# USB-hub.net
KiCad netlist of a schematic drawn in Altium Designer
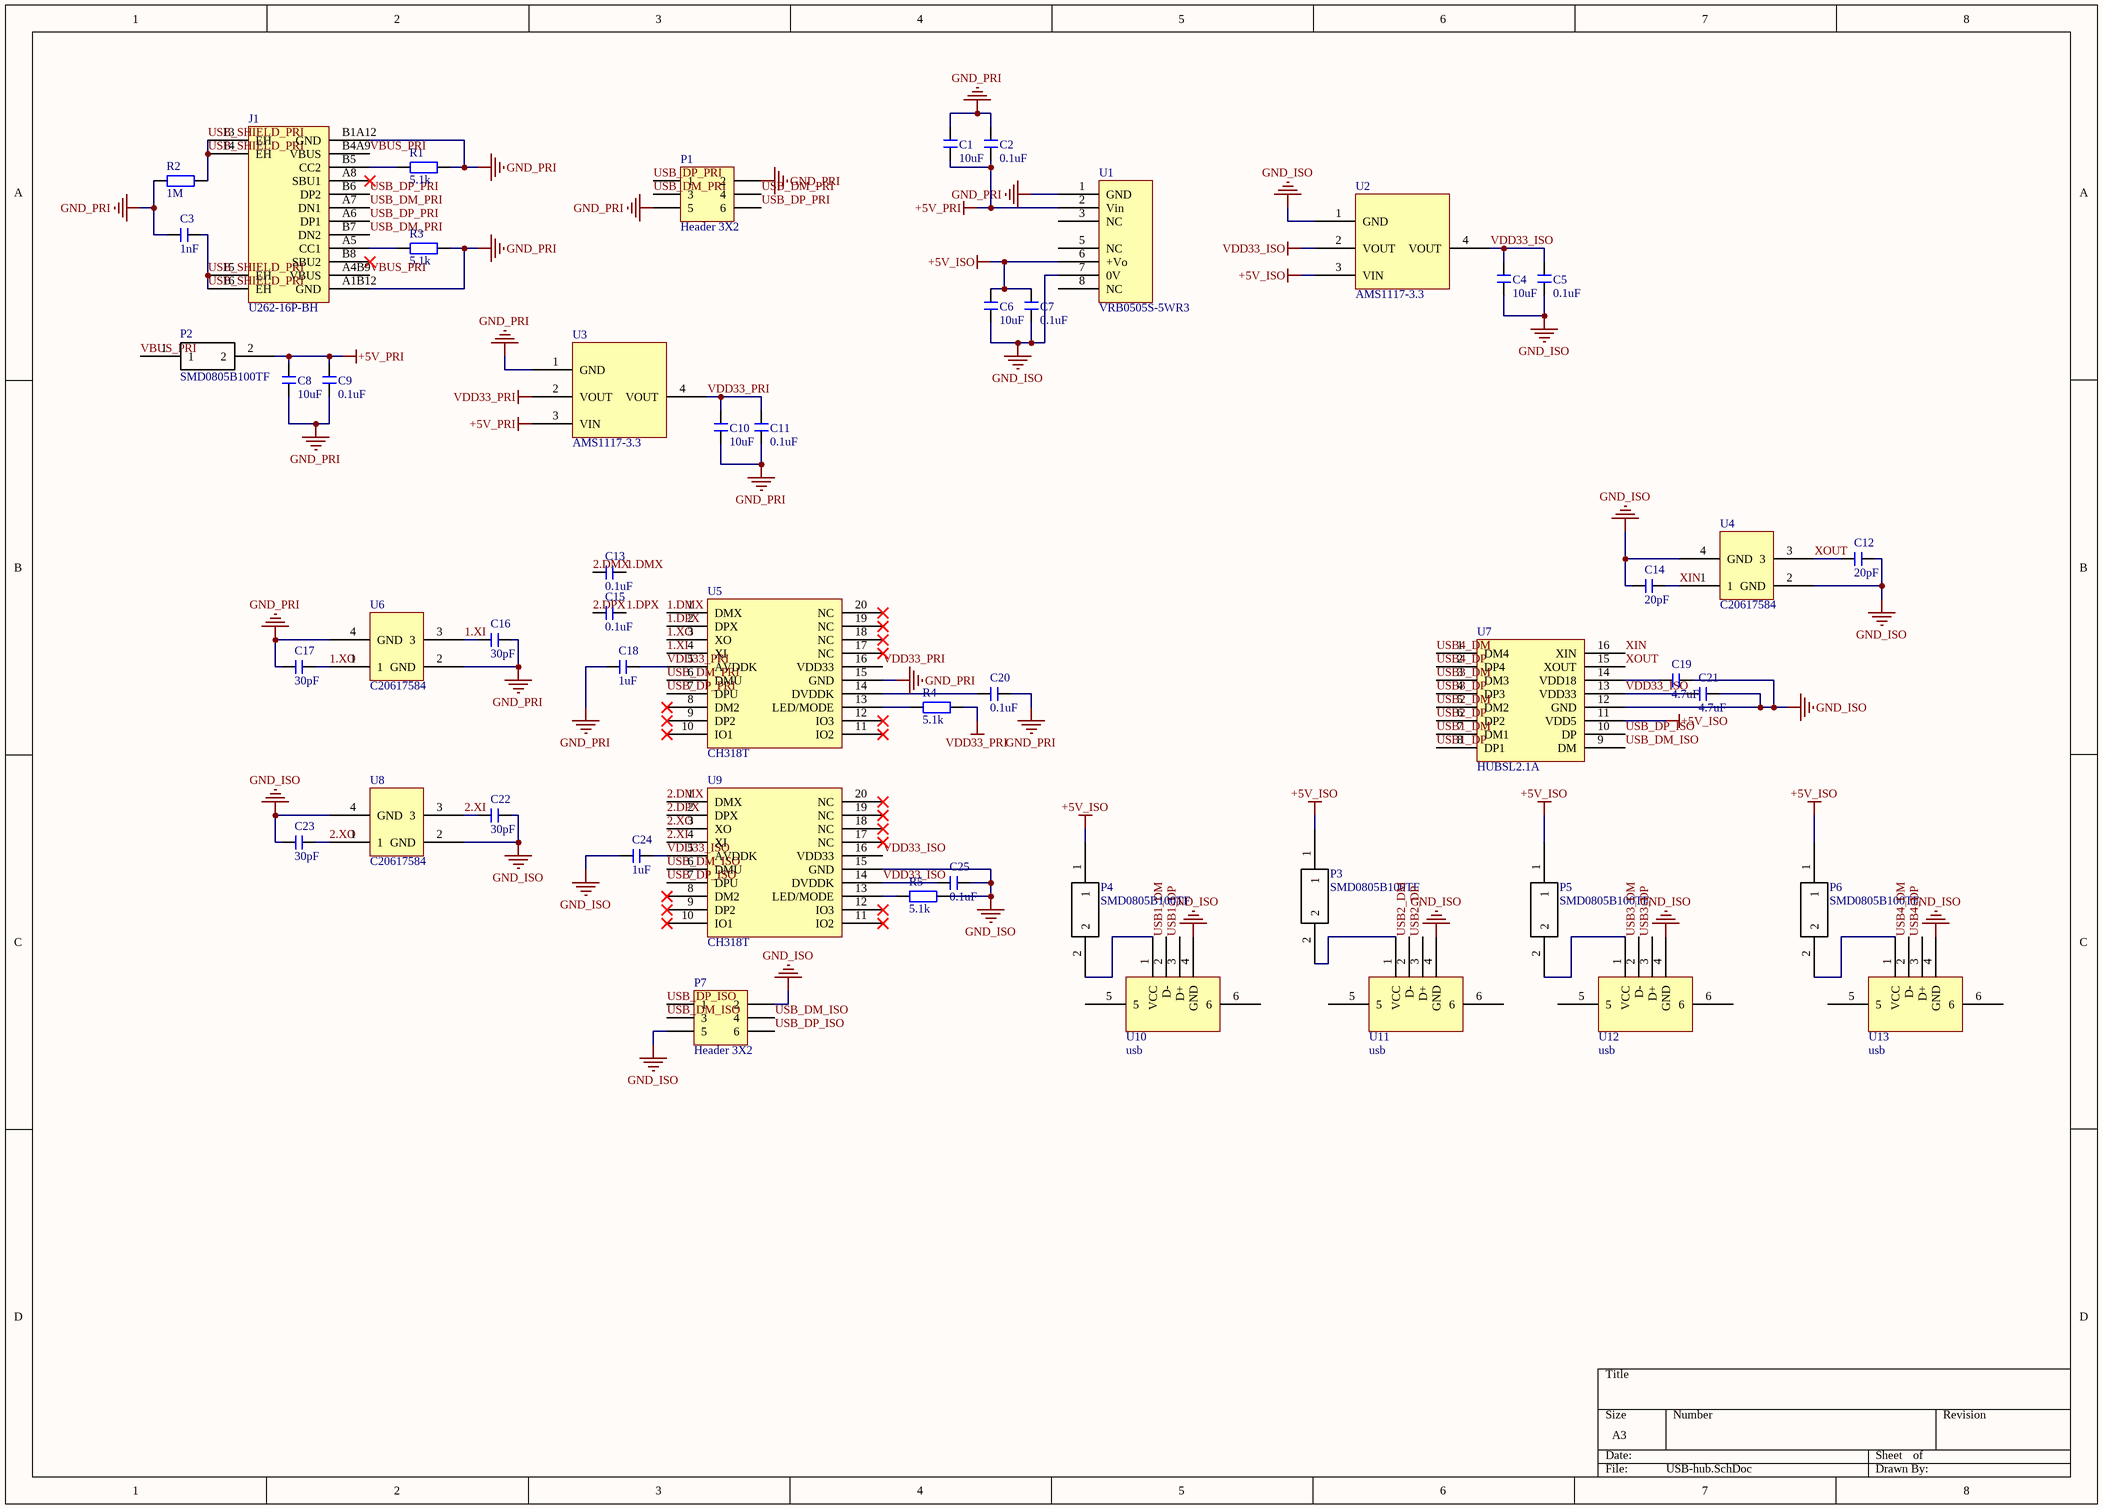
[diagram p0: USB-hub.SchDoc]

(export (version "E")
  (design (tool "Eeschema 10.0.6"))
  (components
    (comp (ref "C1")
      (value "10uF")
      (footprint "C 0603_L")
      (description "贴片电容")
      (libsource (lib "0.1 - 电阻-电容-电感") (part "C"))
    )
    (comp (ref "C2")
      (value "0.1uF")
      (footprint "C 0603_L")
      (description "贴片电容")
      (libsource (lib "0.1 - 电阻-电容-电感") (part "C"))
    )
    (comp (ref "C3")
      (value "1nF")
      (footprint "C 0603_L")
      (description "贴片电容")
      (libsource (lib "0.1 - 电阻-电容-电感") (part "C"))
    )
    (comp (ref "C4")
      (value "10uF")
      (footprint "C 0603_L")
      (description "贴片电容")
      (libsource (lib "0.1 - 电阻-电容-电感") (part "C"))
    )
    (comp (ref "C5")
      (value "0.1uF")
      (footprint "C 0603_L")
      (description "贴片电容")
      (libsource (lib "0.1 - 电阻-电容-电感") (part "C"))
    )
    (comp (ref "C6")
      (value "10uF")
      (footprint "C 0603_L")
      (description "贴片电容")
      (libsource (lib "0.1 - 电阻-电容-电感") (part "C"))
    )
    (comp (ref "C7")
      (value "0.1uF")
      (footprint "C 0603_L")
      (description "贴片电容")
      (libsource (lib "0.1 - 电阻-电容-电感") (part "C"))
    )
    (comp (ref "C8")
      (value "10uF")
      (footprint "C 0603_L")
      (description "贴片电容")
      (libsource (lib "0.1 - 电阻-电容-电感") (part "C"))
    )
    (comp (ref "C9")
      (value "0.1uF")
      (footprint "C 0603_L")
      (description "贴片电容")
      (libsource (lib "0.1 - 电阻-电容-电感") (part "C"))
    )
    (comp (ref "C10")
      (value "10uF")
      (footprint "C 0603_L")
      (description "贴片电容")
      (libsource (lib "0.1 - 电阻-电容-电感") (part "C"))
    )
    (comp (ref "C11")
      (value "0.1uF")
      (footprint "C 0603_L")
      (description "贴片电容")
      (libsource (lib "0.1 - 电阻-电容-电感") (part "C"))
    )
    (comp (ref "C12")
      (value "20pF")
      (footprint "C 0603_L")
      (description "贴片电容")
      (libsource (lib "0.1 - 电阻-电容-电感") (part "C"))
    )
    (comp (ref "C13")
      (value "0.1uF")
      (footprint "C 0603_L")
      (description "贴片电容")
      (libsource (lib "0.1 - 电阻-电容-电感") (part "C"))
    )
    (comp (ref "C14")
      (value "20pF")
      (footprint "C 0603_L")
      (description "贴片电容")
      (libsource (lib "0.1 - 电阻-电容-电感") (part "C"))
    )
    (comp (ref "C15")
      (value "0.1uF")
      (footprint "C 0603_L")
      (description "贴片电容")
      (libsource (lib "0.1 - 电阻-电容-电感") (part "C"))
    )
    (comp (ref "C16")
      (value "30pF")
      (footprint "C 0603_L")
      (description "贴片电容")
      (libsource (lib "0.1 - 电阻-电容-电感") (part "C"))
    )
    (comp (ref "C17")
      (value "30pF")
      (footprint "C 0603_L")
      (description "贴片电容")
      (libsource (lib "0.1 - 电阻-电容-电感") (part "C"))
    )
    (comp (ref "C18")
      (value "1uF")
      (footprint "C 0603_L")
      (description "贴片电容")
      (libsource (lib "0.1 - 电阻-电容-电感") (part "C"))
    )
    (comp (ref "C19")
      (value "4.7uF")
      (footprint "C 0603_L")
      (description "贴片电容")
      (libsource (lib "0.1 - 电阻-电容-电感") (part "C"))
    )
    (comp (ref "C20")
      (value "0.1uF")
      (footprint "C 0603_L")
      (description "贴片电容")
      (libsource (lib "0.1 - 电阻-电容-电感") (part "C"))
    )
    (comp (ref "C21")
      (value "4.7uF")
      (footprint "C 0603_L")
      (description "贴片电容")
      (libsource (lib "0.1 - 电阻-电容-电感") (part "C"))
    )
    (comp (ref "C22")
      (value "30pF")
      (footprint "C 0603_L")
      (description "贴片电容")
      (libsource (lib "0.1 - 电阻-电容-电感") (part "C"))
    )
    (comp (ref "C23")
      (value "30pF")
      (footprint "C 0603_L")
      (description "贴片电容")
      (libsource (lib "0.1 - 电阻-电容-电感") (part "C"))
    )
    (comp (ref "C24")
      (value "1uF")
      (footprint "C 0603_L")
      (description "贴片电容")
      (libsource (lib "0.1 - 电阻-电容-电感") (part "C"))
    )
    (comp (ref "C25")
      (value "0.1uF")
      (footprint "C 0603_L")
      (description "贴片电容")
      (libsource (lib "0.1 - 电阻-电容-电感") (part "C"))
    )
    (comp (ref "J1") (value "U262‑16P‑BH") (footprint "USB-hub") (libsource (lib "USB-hub") (part "type_c")))
    (comp (ref "P1")
      (value "Header 3X2")
      (footprint "SOT-6")
      (description "Header, 3-Pin, Dual row")
      (fields (field (name "PUBLISHER") "Altium Limited"))
      (libsource (lib "Miscellaneous Connectors") (part "Header 3X2"))
    )
    (comp (ref "P2")
      (value "SMD0805B100TF")
      (footprint "SMD0805B100TF")
      (libsource (lib "USB-hub") (part "SMD0805B100TF"))
    )
    (comp (ref "P3")
      (value "SMD0805B100TF")
      (footprint "SMD0805B100TF")
      (libsource (lib "USB-hub") (part "SMD0805B100TF"))
    )
    (comp (ref "P4")
      (value "SMD0805B100TF")
      (footprint "SMD0805B100TF")
      (libsource (lib "USB-hub") (part "SMD0805B100TF"))
    )
    (comp (ref "P5")
      (value "SMD0805B100TF")
      (footprint "SMD0805B100TF")
      (libsource (lib "USB-hub") (part "SMD0805B100TF"))
    )
    (comp (ref "P6")
      (value "SMD0805B100TF")
      (footprint "SMD0805B100TF")
      (libsource (lib "USB-hub") (part "SMD0805B100TF"))
    )
    (comp (ref "P7")
      (value "Header 3X2")
      (footprint "SOT-6")
      (description "Header, 3-Pin, Dual row")
      (fields (field (name "PUBLISHER") "Altium Limited"))
      (libsource (lib "Miscellaneous Connectors") (part "Header 3X2"))
    )
    (comp (ref "R1")
      (value "5.1k")
      (footprint "R 0603_L")
      (description "贴片电阻")
      (fields (field (name "版权归属") "来自淘宝 ID：黄晶宝石"))
      (libsource (lib "0.1 - 电阻-电容-电感") (part "R"))
    )
    (comp (ref "R2")
      (value "1M")
      (footprint "R 0603_L")
      (description "贴片电阻")
      (fields (field (name "版权归属") "来自淘宝 ID：黄晶宝石"))
      (libsource (lib "0.1 - 电阻-电容-电感") (part "R"))
    )
    (comp (ref "R3")
      (value "5.1k")
      (footprint "R 0603_L")
      (description "贴片电阻")
      (fields (field (name "版权归属") "来自淘宝 ID：黄晶宝石"))
      (libsource (lib "0.1 - 电阻-电容-电感") (part "R"))
    )
    (comp (ref "R4")
      (value "5.1k")
      (footprint "R 0603_L")
      (description "贴片电阻")
      (fields (field (name "版权归属") "来自淘宝 ID：黄晶宝石"))
      (libsource (lib "0.1 - 电阻-电容-电感") (part "R"))
    )
    (comp (ref "R5")
      (value "5.1k")
      (footprint "R 0603_L")
      (description "贴片电阻")
      (fields (field (name "版权归属") "来自淘宝 ID：黄晶宝石"))
      (libsource (lib "0.1 - 电阻-电容-电感") (part "R"))
    )
    (comp (ref "U1")
      (value "VRB0505S‑5WR3")
      (footprint "VRB0505S_5WR3")
      (libsource (lib "USB-hub") (part "VRB0505S‑5WR3"))
    )
    (comp (ref "U2")
      (value "AMS1117-3.3")
      (footprint "AMS1117-3.3")
      (libsource (lib "USB-hub") (part "AMS1117-3.3"))
    )
    (comp (ref "U3")
      (value "AMS1117-3.3")
      (footprint "AMS1117-3.3")
      (libsource (lib "USB-hub") (part "AMS1117-3.3"))
    )
    (comp (ref "U4")
      (value "C20617584")
      (footprint "C20617584")
      (libsource (lib "USB-hub") (part "C20617584"))
    )
    (comp (ref "U5") (value "CH318T") (footprint "CH318T") (libsource (lib "USB-hub") (part "CH318T")))
    (comp (ref "U6")
      (value "C20617584")
      (footprint "C20617584")
      (libsource (lib "USB-hub") (part "C20617584"))
    )
    (comp (ref "U7")
      (value "HUBSL2.1A")
      (footprint "HUBSL2.1A")
      (libsource (lib "USB-hub") (part "HUBSL2.1A"))
    )
    (comp (ref "U8")
      (value "C20617584")
      (footprint "C20617584")
      (libsource (lib "USB-hub") (part "C20617584"))
    )
    (comp (ref "U9") (value "CH318T") (footprint "CH318T") (libsource (lib "USB-hub") (part "CH318T")))
    (comp (ref "U10") (value "usb") (footprint "usb") (libsource (lib "USB-hub") (part "usb")))
    (comp (ref "U11") (value "usb") (footprint "usb") (libsource (lib "USB-hub") (part "usb")))
    (comp (ref "U12") (value "usb") (footprint "usb") (libsource (lib "USB-hub") (part "usb")))
    (comp (ref "U13") (value "usb") (footprint "usb") (libsource (lib "USB-hub") (part "usb")))
  )
  (nets
    (net (code "1") (name "+5V_ISO") (class "Default")
      (node (ref "C6") (pin "2") (pinfunction "2_2") (pintype "passive"))
      (node (ref "C7") (pin "2") (pinfunction "2_2") (pintype "passive"))
      (node (ref "P3") (pin "1") (pinfunction "1_1") (pintype "passive"))
      (node (ref "P4") (pin "1") (pinfunction "1_1") (pintype "passive"))
      (node (ref "P5") (pin "1") (pinfunction "1_1") (pintype "passive"))
      (node (ref "P6") (pin "1") (pinfunction "1_1") (pintype "passive"))
      (node (ref "U1") (pin "6") (pinfunction "+Vo_6") (pintype "passive"))
      (node (ref "U2") (pin "3") (pinfunction "VIN_3") (pintype "passive"))
      (node (ref "U7") (pin "11") (pinfunction "VDD5_11") (pintype "passive"))
    )
    (net (code "2") (name "+5V_PRI") (class "Default")
      (node (ref "C1") (pin "1") (pinfunction "1_1") (pintype "passive"))
      (node (ref "C2") (pin "1") (pinfunction "1_1") (pintype "passive"))
      (node (ref "C8") (pin "1") (pinfunction "1_1") (pintype "passive"))
      (node (ref "C9") (pin "1") (pinfunction "1_1") (pintype "passive"))
      (node (ref "P2") (pin "2") (pinfunction "2_2") (pintype "passive"))
      (node (ref "U1") (pin "2") (pinfunction "Vin_2") (pintype "passive"))
      (node (ref "U3") (pin "3") (pinfunction "VIN_3") (pintype "passive"))
    )
    (net (code "3") (name "/1.DMX") (class "Default")
      (node (ref "C13") (pin "2") (pinfunction "2_2") (pintype "passive"))
      (node (ref "U5") (pin "1") (pinfunction "DMX_1") (pintype "passive"))
    )
    (net (code "4") (name "/1.DPX") (class "Default")
      (node (ref "C15") (pin "2") (pinfunction "2_2") (pintype "passive"))
      (node (ref "U5") (pin "2") (pinfunction "DPX_2") (pintype "passive"))
    )
    (net (code "5") (name "/1.XI") (class "Default")
      (node (ref "C16") (pin "1") (pinfunction "1_1") (pintype "passive"))
      (node (ref "U5") (pin "4") (pinfunction "XI_4") (pintype "passive"))
      (node (ref "U6") (pin "3") (pinfunction "3_3") (pintype "passive"))
    )
    (net (code "6") (name "/1.XO") (class "Default")
      (node (ref "C17") (pin "1") (pinfunction "1_1") (pintype "passive"))
      (node (ref "U5") (pin "3") (pinfunction "XO_3") (pintype "passive"))
      (node (ref "U6") (pin "1") (pinfunction "1_1") (pintype "passive"))
    )
    (net (code "7") (name "/2.DMX") (class "Default")
      (node (ref "C13") (pin "1") (pinfunction "1_1") (pintype "passive"))
      (node (ref "U9") (pin "1") (pinfunction "DMX_1") (pintype "passive"))
    )
    (net (code "8") (name "/2.DPX") (class "Default")
      (node (ref "C15") (pin "1") (pinfunction "1_1") (pintype "passive"))
      (node (ref "U9") (pin "2") (pinfunction "DPX_2") (pintype "passive"))
    )
    (net (code "9") (name "/2.XI") (class "Default")
      (node (ref "C22") (pin "1") (pinfunction "1_1") (pintype "passive"))
      (node (ref "U8") (pin "3") (pinfunction "3_3") (pintype "passive"))
      (node (ref "U9") (pin "4") (pinfunction "XI_4") (pintype "passive"))
    )
    (net (code "10") (name "/2.XO") (class "Default")
      (node (ref "C23") (pin "1") (pinfunction "1_1") (pintype "passive"))
      (node (ref "U8") (pin "1") (pinfunction "1_1") (pintype "passive"))
      (node (ref "U9") (pin "3") (pinfunction "XO_3") (pintype "passive"))
    )
    (net (code "11") (name "/USB1_DM") (class "Default")
      (node (ref "U10") (pin "2") (pinfunction "D-_2") (pintype "passive"))
      (node (ref "U7") (pin "7") (pinfunction "DM1_7") (pintype "passive"))
    )
    (net (code "12") (name "/USB1_DP") (class "Default")
      (node (ref "U10") (pin "3") (pinfunction "D+_3") (pintype "passive"))
      (node (ref "U7") (pin "8") (pinfunction "DP1_8") (pintype "passive"))
    )
    (net (code "13") (name "/USB2_DM") (class "Default")
      (node (ref "U11") (pin "2") (pinfunction "D-_2") (pintype "passive"))
      (node (ref "U7") (pin "5") (pinfunction "DM2_5") (pintype "passive"))
    )
    (net (code "14") (name "/USB2_DP") (class "Default")
      (node (ref "U11") (pin "3") (pinfunction "D+_3") (pintype "passive"))
      (node (ref "U7") (pin "6") (pinfunction "DP2_6") (pintype "passive"))
    )
    (net (code "15") (name "/USB3_DM") (class "Default")
      (node (ref "U12") (pin "2") (pinfunction "D-_2") (pintype "passive"))
      (node (ref "U7") (pin "3") (pinfunction "DM3_3") (pintype "passive"))
    )
    (net (code "16") (name "/USB3_DP") (class "Default")
      (node (ref "U12") (pin "3") (pinfunction "D+_3") (pintype "passive"))
      (node (ref "U7") (pin "4") (pinfunction "DP3_4") (pintype "passive"))
    )
    (net (code "17") (name "/USB4_DM") (class "Default")
      (node (ref "U13") (pin "2") (pinfunction "D-_2") (pintype "passive"))
      (node (ref "U7") (pin "1") (pinfunction "DM4_1") (pintype "passive"))
    )
    (net (code "18") (name "/USB4_DP") (class "Default")
      (node (ref "U13") (pin "3") (pinfunction "D+_3") (pintype "passive"))
      (node (ref "U7") (pin "2") (pinfunction "DP4_2") (pintype "passive"))
    )
    (net (code "19") (name "/USB_DM_ISO") (class "Default")
      (node (ref "P7") (pin "3") (pinfunction "3_3") (pintype "passive"))
      (node (ref "P7") (pin "4") (pinfunction "4_4") (pintype "passive"))
      (node (ref "U7") (pin "9") (pinfunction "DM_9") (pintype "passive"))
      (node (ref "U9") (pin "6") (pinfunction "DMU_6") (pintype "passive"))
    )
    (net (code "20") (name "/USB_DM_PRI") (class "Default")
      (node (ref "J1") (pin "A7") (pinfunction "DN1_A7") (pintype "passive"))
      (node (ref "J1") (pin "B7") (pinfunction "DN2_B7") (pintype "passive"))
      (node (ref "P1") (pin "3") (pinfunction "3_3") (pintype "passive"))
      (node (ref "P1") (pin "4") (pinfunction "4_4") (pintype "passive"))
      (node (ref "U5") (pin "6") (pinfunction "DMU_6") (pintype "passive"))
    )
    (net (code "21") (name "/USB_DP_ISO") (class "Default")
      (node (ref "P7") (pin "1") (pinfunction "1_1") (pintype "passive"))
      (node (ref "P7") (pin "6") (pinfunction "6_6") (pintype "passive"))
      (node (ref "U7") (pin "10") (pinfunction "DP_10") (pintype "passive"))
      (node (ref "U9") (pin "7") (pinfunction "DPU_7") (pintype "passive"))
    )
    (net (code "22") (name "/USB_DP_PRI") (class "Default")
      (node (ref "J1") (pin "A6") (pinfunction "DP1_A6") (pintype "passive"))
      (node (ref "J1") (pin "B6") (pinfunction "DP2_B6") (pintype "passive"))
      (node (ref "P1") (pin "1") (pinfunction "1_1") (pintype "passive"))
      (node (ref "P1") (pin "6") (pinfunction "6_6") (pintype "passive"))
      (node (ref "U5") (pin "7") (pinfunction "DPU_7") (pintype "passive"))
    )
    (net (code "23") (name "/USB_SHIELD_PRI") (class "Default")
      (node (ref "C3") (pin "2") (pinfunction "2_2") (pintype "passive"))
      (node (ref "J1") (pin "13") (pinfunction "EH_13") (pintype "passive"))
      (node (ref "J1") (pin "14") (pinfunction "EH_14") (pintype "passive"))
      (node (ref "J1") (pin "15") (pinfunction "EH_15") (pintype "passive"))
      (node (ref "J1") (pin "16") (pinfunction "EH_16") (pintype "passive"))
      (node (ref "R2") (pin "2") (pinfunction "2_2") (pintype "passive"))
    )
    (net (code "24") (name "/VBUS_PRI") (class "Default")
      (node (ref "J1") (pin "A4B9") (pinfunction "VBUS_A4B9") (pintype "passive"))
      (node (ref "J1") (pin "B4A9") (pinfunction "VBUS_B4A9") (pintype "passive"))
      (node (ref "P2") (pin "1") (pinfunction "1_1") (pintype "passive"))
    )
    (net (code "25") (name "/XIN") (class "Default")
      (node (ref "C14") (pin "1") (pinfunction "1_1") (pintype "passive"))
      (node (ref "U4") (pin "1") (pinfunction "1_1") (pintype "passive"))
      (node (ref "U7") (pin "16") (pinfunction "XIN_16") (pintype "passive"))
    )
    (net (code "26") (name "/XOUT") (class "Default")
      (node (ref "C12") (pin "2") (pinfunction "2_2") (pintype "passive"))
      (node (ref "U4") (pin "3") (pinfunction "3_3") (pintype "passive"))
      (node (ref "U7") (pin "15") (pinfunction "XOUT_15") (pintype "passive"))
    )
    (net (code "27") (name "GND_ISO") (class "Default")
      (node (ref "C12") (pin "1") (pinfunction "1_1") (pintype "passive"))
      (node (ref "C14") (pin "2") (pinfunction "2_2") (pintype "passive"))
      (node (ref "C19") (pin "1") (pinfunction "1_1") (pintype "passive"))
      (node (ref "C21") (pin "1") (pinfunction "1_1") (pintype "passive"))
      (node (ref "C22") (pin "2") (pinfunction "2_2") (pintype "passive"))
      (node (ref "C23") (pin "2") (pinfunction "2_2") (pintype "passive"))
      (node (ref "C24") (pin "1") (pinfunction "1_1") (pintype "passive"))
      (node (ref "C25") (pin "2") (pinfunction "2_2") (pintype "passive"))
      (node (ref "C4") (pin "2") (pinfunction "2_2") (pintype "passive"))
      (node (ref "C5") (pin "2") (pinfunction "2_2") (pintype "passive"))
      (node (ref "C6") (pin "1") (pinfunction "1_1") (pintype "passive"))
      (node (ref "C7") (pin "1") (pinfunction "1_1") (pintype "passive"))
      (node (ref "P7") (pin "2") (pinfunction "2_2") (pintype "passive"))
      (node (ref "P7") (pin "5") (pinfunction "5_5") (pintype "passive"))
      (node (ref "R5") (pin "2") (pinfunction "2_2") (pintype "passive"))
      (node (ref "U1") (pin "7") (pinfunction "0V_7") (pintype "passive"))
      (node (ref "U10") (pin "4") (pinfunction "GND_4") (pintype "passive"))
      (node (ref "U11") (pin "4") (pinfunction "GND_4") (pintype "passive"))
      (node (ref "U12") (pin "4") (pinfunction "GND_4") (pintype "passive"))
      (node (ref "U13") (pin "4") (pinfunction "GND_4") (pintype "passive"))
      (node (ref "U2") (pin "1") (pinfunction "GND_1") (pintype "passive"))
      (node (ref "U4") (pin "2") (pinfunction "GND_2") (pintype "passive"))
      (node (ref "U4") (pin "4") (pinfunction "GND_4") (pintype "passive"))
      (node (ref "U7") (pin "12") (pinfunction "GND_12") (pintype "passive"))
      (node (ref "U8") (pin "2") (pinfunction "GND_2") (pintype "passive"))
      (node (ref "U8") (pin "4") (pinfunction "GND_4") (pintype "passive"))
      (node (ref "U9") (pin "15") (pinfunction "GND_15") (pintype "passive"))
    )
    (net (code "28") (name "GND_PRI") (class "Default")
      (node (ref "C1") (pin "2") (pinfunction "2_2") (pintype "passive"))
      (node (ref "C10") (pin "2") (pinfunction "2_2") (pintype "passive"))
      (node (ref "C11") (pin "2") (pinfunction "2_2") (pintype "passive"))
      (node (ref "C16") (pin "2") (pinfunction "2_2") (pintype "passive"))
      (node (ref "C17") (pin "2") (pinfunction "2_2") (pintype "passive"))
      (node (ref "C18") (pin "1") (pinfunction "1_1") (pintype "passive"))
      (node (ref "C2") (pin "2") (pinfunction "2_2") (pintype "passive"))
      (node (ref "C20") (pin "2") (pinfunction "2_2") (pintype "passive"))
      (node (ref "C3") (pin "1") (pinfunction "1_1") (pintype "passive"))
      (node (ref "C8") (pin "2") (pinfunction "2_2") (pintype "passive"))
      (node (ref "C9") (pin "2") (pinfunction "2_2") (pintype "passive"))
      (node (ref "J1") (pin "A1B12") (pinfunction "GND_A1B12") (pintype "passive"))
      (node (ref "J1") (pin "B1A12") (pinfunction "GND_B1A12") (pintype "passive"))
      (node (ref "P1") (pin "2") (pinfunction "2_2") (pintype "passive"))
      (node (ref "P1") (pin "5") (pinfunction "5_5") (pintype "passive"))
      (node (ref "R1") (pin "2") (pinfunction "2_2") (pintype "passive"))
      (node (ref "R2") (pin "1") (pinfunction "1_1") (pintype "passive"))
      (node (ref "R3") (pin "2") (pinfunction "2_2") (pintype "passive"))
      (node (ref "U1") (pin "1") (pinfunction "GND_1") (pintype "passive"))
      (node (ref "U3") (pin "1") (pinfunction "GND_1") (pintype "passive"))
      (node (ref "U5") (pin "15") (pinfunction "GND_15") (pintype "passive"))
      (node (ref "U6") (pin "2") (pinfunction "GND_2") (pintype "passive"))
      (node (ref "U6") (pin "4") (pinfunction "GND_4") (pintype "passive"))
    )
    (net (code "29") (name "Net-(J1-CC1)") (class "Default")
      (node (ref "J1") (pin "A5") (pinfunction "CC1_A5") (pintype "passive"))
      (node (ref "R3") (pin "1") (pinfunction "1_1") (pintype "passive"))
    )
    (net (code "30") (name "Net-(J1-CC2)") (class "Default")
      (node (ref "J1") (pin "B5") (pinfunction "CC2_B5") (pintype "passive"))
      (node (ref "R1") (pin "1") (pinfunction "1_1") (pintype "passive"))
    )
    (net (code "31") (name "Net-(U5-DVDDK)") (class "Default")
      (node (ref "C20") (pin "1") (pinfunction "1_1") (pintype "passive"))
      (node (ref "U5") (pin "14") (pinfunction "DVDDK_14") (pintype "passive"))
    )
    (net (code "32") (name "Net-(U5-LED{slash}MODE)") (class "Default")
      (node (ref "R4") (pin "1") (pinfunction "1_1") (pintype "passive"))
      (node (ref "U5") (pin "13") (pinfunction "LED/MODE_13") (pintype "passive"))
    )
    (net (code "33") (name "Net-(U7-VDD18)") (class "Default")
      (node (ref "C19") (pin "2") (pinfunction "2_2") (pintype "passive"))
      (node (ref "U7") (pin "14") (pinfunction "VDD18_14") (pintype "passive"))
    )
    (net (code "34") (name "Net-(U9-LED{slash}MODE)") (class "Default")
      (node (ref "R5") (pin "1") (pinfunction "1_1") (pintype "passive"))
      (node (ref "U9") (pin "13") (pinfunction "LED/MODE_13") (pintype "passive"))
    )
    (net (code "35") (name "Net-(U10-VCC)") (class "Default")
      (node (ref "P4") (pin "2") (pinfunction "2_2") (pintype "passive"))
      (node (ref "U10") (pin "1") (pinfunction "VCC_1") (pintype "passive"))
    )
    (net (code "36") (name "Net-(U11-VCC)") (class "Default")
      (node (ref "P3") (pin "2") (pinfunction "2_2") (pintype "passive"))
      (node (ref "U11") (pin "1") (pinfunction "VCC_1") (pintype "passive"))
    )
    (net (code "37") (name "Net-(U12-VCC)") (class "Default")
      (node (ref "P5") (pin "2") (pinfunction "2_2") (pintype "passive"))
      (node (ref "U12") (pin "1") (pinfunction "VCC_1") (pintype "passive"))
    )
    (net (code "38") (name "Net-(U13-VCC)") (class "Default")
      (node (ref "P6") (pin "2") (pinfunction "2_2") (pintype "passive"))
      (node (ref "U13") (pin "1") (pinfunction "VCC_1") (pintype "passive"))
    )
    (net (code "39") (name "VDD33_ISO") (class "Default")
      (node (ref "C21") (pin "2") (pinfunction "2_2") (pintype "passive"))
      (node (ref "C24") (pin "2") (pinfunction "2_2") (pintype "passive"))
      (node (ref "C25") (pin "1") (pinfunction "1_1") (pintype "passive"))
      (node (ref "C4") (pin "1") (pinfunction "1_1") (pintype "passive"))
      (node (ref "C5") (pin "1") (pinfunction "1_1") (pintype "passive"))
      (node (ref "U2") (pin "2") (pinfunction "VOUT_2") (pintype "passive"))
      (node (ref "U2") (pin "4") (pinfunction "VOUT_4") (pintype "passive"))
      (node (ref "U7") (pin "13") (pinfunction "VDD33_13") (pintype "passive"))
      (node (ref "U9") (pin "14") (pinfunction "DVDDK_14") (pintype "passive"))
      (node (ref "U9") (pin "16") (pinfunction "VDD33_16") (pintype "passive"))
      (node (ref "U9") (pin "5") (pinfunction "AVDDK_5") (pintype "passive"))
    )
    (net (code "40") (name "VDD33_PRI") (class "Default")
      (node (ref "C10") (pin "1") (pinfunction "1_1") (pintype "passive"))
      (node (ref "C11") (pin "1") (pinfunction "1_1") (pintype "passive"))
      (node (ref "C18") (pin "2") (pinfunction "2_2") (pintype "passive"))
      (node (ref "R4") (pin "2") (pinfunction "2_2") (pintype "passive"))
      (node (ref "U3") (pin "2") (pinfunction "VOUT_2") (pintype "passive"))
      (node (ref "U3") (pin "4") (pinfunction "VOUT_4") (pintype "passive"))
      (node (ref "U5") (pin "16") (pinfunction "VDD33_16") (pintype "passive"))
      (node (ref "U5") (pin "5") (pinfunction "AVDDK_5") (pintype "passive"))
    )
    (net (code "41") (name "unconnected-(J1-SBU1-PadA8)") (class "Default")
      (node (ref "J1") (pin "A8") (pinfunction "SBU1_A8") (pintype "passive+no_connect"))
    )
    (net (code "42") (name "unconnected-(J1-SBU2-PadB8)") (class "Default")
      (node (ref "J1") (pin "B8") (pinfunction "SBU2_B8") (pintype "passive+no_connect"))
    )
    (net (code "43") (name "unconnected-(U1-NC-Pad3)") (class "Default")
      (node (ref "U1") (pin "3") (pinfunction "NC_3") (pintype "passive"))
    )
    (net (code "44") (name "unconnected-(U1-NC-Pad5)") (class "Default")
      (node (ref "U1") (pin "5") (pinfunction "NC_5") (pintype "passive"))
    )
    (net (code "45") (name "unconnected-(U1-NC-Pad8)") (class "Default")
      (node (ref "U1") (pin "8") (pinfunction "NC_8") (pintype "passive"))
    )
    (net (code "46") (name "unconnected-(U5-DM2-Pad8)") (class "Default")
      (node (ref "U5") (pin "8") (pinfunction "DM2_8") (pintype "passive+no_connect"))
    )
    (net (code "47") (name "unconnected-(U5-DP2-Pad9)") (class "Default")
      (node (ref "U5") (pin "9") (pinfunction "DP2_9") (pintype "passive+no_connect"))
    )
    (net (code "48") (name "unconnected-(U5-IO1-Pad10)") (class "Default")
      (node (ref "U5") (pin "10") (pinfunction "IO1_10") (pintype "passive+no_connect"))
    )
    (net (code "49") (name "unconnected-(U5-IO2-Pad11)") (class "Default")
      (node (ref "U5") (pin "11") (pinfunction "IO2_11") (pintype "passive+no_connect"))
    )
    (net (code "50") (name "unconnected-(U5-IO3-Pad12)") (class "Default")
      (node (ref "U5") (pin "12") (pinfunction "IO3_12") (pintype "passive+no_connect"))
    )
    (net (code "51") (name "unconnected-(U5-NC-Pad17)") (class "Default")
      (node (ref "U5") (pin "17") (pinfunction "NC_17") (pintype "passive+no_connect"))
    )
    (net (code "52") (name "unconnected-(U5-NC-Pad18)") (class "Default")
      (node (ref "U5") (pin "18") (pinfunction "NC_18") (pintype "passive+no_connect"))
    )
    (net (code "53") (name "unconnected-(U5-NC-Pad19)") (class "Default")
      (node (ref "U5") (pin "19") (pinfunction "NC_19") (pintype "passive+no_connect"))
    )
    (net (code "54") (name "unconnected-(U5-NC-Pad20)") (class "Default")
      (node (ref "U5") (pin "20") (pinfunction "NC_20") (pintype "passive+no_connect"))
    )
    (net (code "55") (name "unconnected-(U9-DM2-Pad8)") (class "Default")
      (node (ref "U9") (pin "8") (pinfunction "DM2_8") (pintype "passive+no_connect"))
    )
    (net (code "56") (name "unconnected-(U9-DP2-Pad9)") (class "Default")
      (node (ref "U9") (pin "9") (pinfunction "DP2_9") (pintype "passive+no_connect"))
    )
    (net (code "57") (name "unconnected-(U9-IO1-Pad10)") (class "Default")
      (node (ref "U9") (pin "10") (pinfunction "IO1_10") (pintype "passive+no_connect"))
    )
    (net (code "58") (name "unconnected-(U9-IO2-Pad11)") (class "Default")
      (node (ref "U9") (pin "11") (pinfunction "IO2_11") (pintype "passive+no_connect"))
    )
    (net (code "59") (name "unconnected-(U9-IO3-Pad12)") (class "Default")
      (node (ref "U9") (pin "12") (pinfunction "IO3_12") (pintype "passive+no_connect"))
    )
    (net (code "60") (name "unconnected-(U9-NC-Pad17)") (class "Default")
      (node (ref "U9") (pin "17") (pinfunction "NC_17") (pintype "passive+no_connect"))
    )
    (net (code "61") (name "unconnected-(U9-NC-Pad18)") (class "Default")
      (node (ref "U9") (pin "18") (pinfunction "NC_18") (pintype "passive+no_connect"))
    )
    (net (code "62") (name "unconnected-(U9-NC-Pad19)") (class "Default")
      (node (ref "U9") (pin "19") (pinfunction "NC_19") (pintype "passive+no_connect"))
    )
    (net (code "63") (name "unconnected-(U9-NC-Pad20)") (class "Default")
      (node (ref "U9") (pin "20") (pinfunction "NC_20") (pintype "passive+no_connect"))
    )
    (net (code "64") (name "unconnected-(U10-Pad5)") (class "Default")
      (node (ref "U10") (pin "5") (pinfunction "5_5") (pintype "passive"))
    )
    (net (code "65") (name "unconnected-(U10-Pad6)") (class "Default")
      (node (ref "U10") (pin "6") (pinfunction "6_6") (pintype "passive"))
    )
    (net (code "66") (name "unconnected-(U11-Pad5)") (class "Default")
      (node (ref "U11") (pin "5") (pinfunction "5_5") (pintype "passive"))
    )
    (net (code "67") (name "unconnected-(U11-Pad6)") (class "Default")
      (node (ref "U11") (pin "6") (pinfunction "6_6") (pintype "passive"))
    )
    (net (code "68") (name "unconnected-(U12-Pad5)") (class "Default")
      (node (ref "U12") (pin "5") (pinfunction "5_5") (pintype "passive"))
    )
    (net (code "69") (name "unconnected-(U12-Pad6)") (class "Default")
      (node (ref "U12") (pin "6") (pinfunction "6_6") (pintype "passive"))
    )
    (net (code "70") (name "unconnected-(U13-Pad5)") (class "Default")
      (node (ref "U13") (pin "5") (pinfunction "5_5") (pintype "passive"))
    )
    (net (code "71") (name "unconnected-(U13-Pad6)") (class "Default")
      (node (ref "U13") (pin "6") (pinfunction "6_6") (pintype "passive"))
    )
  )
)
